# ADNS-9800_-_v2_1.net
KiCad netlist of a schematic drawn in EAGLE
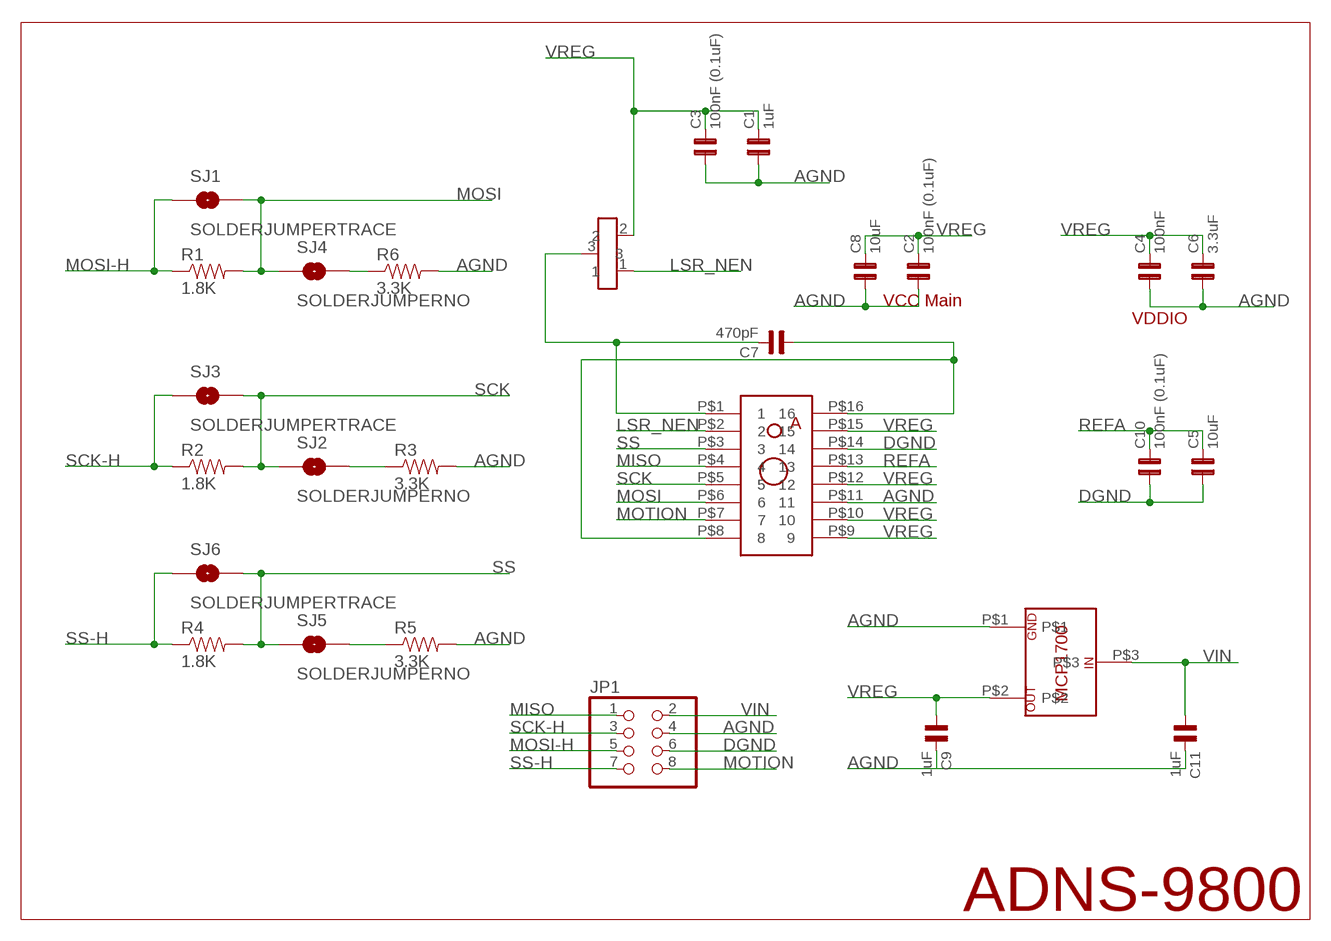
[diagram p0: schematic, sheet 1]

(export (version "E")
  (design (tool "Eeschema 10.0.6"))
  (components
    (comp (ref "C1")
      (value "1uF")
      (footprint "eagle-import:0603")
      (libsource (lib "eagle-import") (part "C0603"))
    )
    (comp (ref "C2")
      (value "100nF (0.1uF)")
      (footprint "eagle-import:0603")
      (libsource (lib "eagle-import") (part "C0603"))
    )
    (comp (ref "C3")
      (value "100nF (0.1uF)")
      (footprint "eagle-import:0603")
      (libsource (lib "eagle-import") (part "C0603"))
    )
    (comp (ref "C4")
      (value "100nF")
      (footprint "eagle-import:0603")
      (libsource (lib "eagle-import") (part "C0603"))
    )
    (comp (ref "C5")
      (value "10uF")
      (footprint "eagle-import:0603")
      (libsource (lib "eagle-import") (part "C0603"))
    )
    (comp (ref "C6")
      (value "3.3uF")
      (footprint "eagle-import:0603")
      (libsource (lib "eagle-import") (part "C0603"))
    )
    (comp (ref "C7")
      (value "470pF")
      (footprint "eagle-import:0603")
      (libsource (lib "eagle-import") (part "C0603"))
    )
    (comp (ref "C8")
      (value "10uF")
      (footprint "eagle-import:0603")
      (libsource (lib "eagle-import") (part "C0603"))
    )
    (comp (ref "C9")
      (value "1uF")
      (footprint "eagle-import:0603")
      (libsource (lib "eagle-import") (part "C0603"))
    )
    (comp (ref "C10")
      (value "100nF (0.1uF)")
      (footprint "eagle-import:0603")
      (libsource (lib "eagle-import") (part "C0603"))
    )
    (comp (ref "C11")
      (value "1uF")
      (footprint "eagle-import:0603")
      (libsource (lib "eagle-import") (part "C0603"))
    )
    (comp (ref "JP1")
      (value "PINHD-2X4")
      (footprint "eagle-import:2X04")
      (libsource (lib "eagle-import") (part "PINHD-2X4"))
    )
    (comp (ref "Q1")
      (value "TRANSISTOR_SC-75")
      (footprint "eagle-import:SC-75_TRANSISTOR")
      (libsource (lib "eagle-import") (part "TRANSISTOR_SC-75"))
    )
    (comp (ref "R1")
      (value "1.8K")
      (footprint "eagle-import:0603-RES")
      (libsource (lib "eagle-import") (part "RESISTOR0603-RES"))
    )
    (comp (ref "R2")
      (value "1.8K")
      (footprint "eagle-import:0603-RES")
      (libsource (lib "eagle-import") (part "RESISTOR0603-RES"))
    )
    (comp (ref "R3")
      (value "3.3K")
      (footprint "eagle-import:0603-RES")
      (libsource (lib "eagle-import") (part "RESISTOR0603-RES"))
    )
    (comp (ref "R4")
      (value "1.8K")
      (footprint "eagle-import:0603-RES")
      (libsource (lib "eagle-import") (part "RESISTOR0603-RES"))
    )
    (comp (ref "R5")
      (value "3.3K")
      (footprint "eagle-import:0603-RES")
      (libsource (lib "eagle-import") (part "RESISTOR0603-RES"))
    )
    (comp (ref "R6")
      (value "3.3K")
      (footprint "eagle-import:0603-RES")
      (libsource (lib "eagle-import") (part "RESISTOR0603-RES"))
    )
    (comp (ref "SJ1")
      (value "SOLDERJUMPERTRACE")
      (footprint "eagle-import:SJ_2S-TRACE")
      (libsource (lib "eagle-import") (part "SOLDERJUMPERTRACE"))
    )
    (comp (ref "SJ2")
      (value "SOLDERJUMPERNO")
      (footprint "eagle-import:SJ_2S-NO")
      (libsource (lib "eagle-import") (part "SOLDERJUMPERNO"))
    )
    (comp (ref "SJ3")
      (value "SOLDERJUMPERTRACE")
      (footprint "eagle-import:SJ_2S-TRACE")
      (libsource (lib "eagle-import") (part "SOLDERJUMPERTRACE"))
    )
    (comp (ref "SJ4")
      (value "SOLDERJUMPERNO")
      (footprint "eagle-import:SJ_2S-NO")
      (libsource (lib "eagle-import") (part "SOLDERJUMPERNO"))
    )
    (comp (ref "SJ5")
      (value "SOLDERJUMPERNO")
      (footprint "eagle-import:SJ_2S-NO")
      (libsource (lib "eagle-import") (part "SOLDERJUMPERNO"))
    )
    (comp (ref "SJ6")
      (value "SOLDERJUMPERTRACE")
      (footprint "eagle-import:SJ_2S-TRACE")
      (libsource (lib "eagle-import") (part "SOLDERJUMPERTRACE"))
    )
    (comp (ref "U$1")
      (value "AVAGO_ADNS-9500")
      (footprint "eagle-import:AVAGO_ADNS-9500")
      (libsource (lib "eagle-import") (part "AVAGO_ADNS-9500"))
    )
    (comp (ref "U$2")
      (value "MCP1700__LDO")
      (footprint "eagle-import:MCP1700__LDO")
      (libsource (lib "eagle-import") (part "MCP1700__LDO"))
    )
  )
  (nets
    (net (code "1") (name "/AGND") (class "Default")
      (node (ref "C1") (pin "1") (pinfunction "1_1") (pintype "passive"))
      (node (ref "C11") (pin "2") (pinfunction "2_2") (pintype "passive"))
      (node (ref "C2") (pin "1") (pinfunction "1_1") (pintype "passive"))
      (node (ref "C3") (pin "1") (pinfunction "1_1") (pintype "passive"))
      (node (ref "C4") (pin "1") (pinfunction "1_1") (pintype "passive"))
      (node (ref "C6") (pin "1") (pinfunction "1_1") (pintype "passive"))
      (node (ref "C8") (pin "1") (pinfunction "1_1") (pintype "passive"))
      (node (ref "C9") (pin "2") (pinfunction "2_2") (pintype "passive"))
      (node (ref "JP1") (pin "4") (pinfunction "4_4") (pintype "passive"))
      (node (ref "R3") (pin "2") (pinfunction "2_2") (pintype "passive"))
      (node (ref "R5") (pin "2") (pinfunction "2_2") (pintype "passive"))
      (node (ref "R6") (pin "2") (pinfunction "2_2") (pintype "passive"))
      (node (ref "U$1") (pin "P$11") (pinfunction "11_P$11") (pintype "bidirectional"))
      (node (ref "U$2") (pin "P$1") (pinfunction "P$1_P$1") (pintype "bidirectional"))
    )
    (net (code "2") (name "/DGND") (class "Default")
      (node (ref "C10") (pin "1") (pinfunction "1_1") (pintype "passive"))
      (node (ref "C5") (pin "1") (pinfunction "1_1") (pintype "passive"))
      (node (ref "JP1") (pin "6") (pinfunction "6_6") (pintype "passive"))
      (node (ref "U$1") (pin "P$14") (pinfunction "14_P$14") (pintype "bidirectional"))
    )
    (net (code "3") (name "/LSR_NEN") (class "Default")
      (node (ref "Q1") (pin "1") (pinfunction "1_1") (pintype "bidirectional"))
      (node (ref "U$1") (pin "P$2") (pinfunction "2_P$2") (pintype "bidirectional"))
    )
    (net (code "4") (name "/MISO") (class "Default")
      (node (ref "JP1") (pin "1") (pinfunction "1_1") (pintype "passive"))
      (node (ref "U$1") (pin "P$4") (pinfunction "4_P$4") (pintype "bidirectional"))
    )
    (net (code "5") (name "/MOSI") (class "Default")
      (node (ref "R1") (pin "2") (pinfunction "2_2") (pintype "passive"))
      (node (ref "SJ1") (pin "2") (pinfunction "2_2") (pintype "passive"))
      (node (ref "SJ4") (pin "1") (pinfunction "1_1") (pintype "passive"))
      (node (ref "U$1") (pin "P$6") (pinfunction "6_P$6") (pintype "bidirectional"))
    )
    (net (code "6") (name "/MOSI-H") (class "Default")
      (node (ref "JP1") (pin "5") (pinfunction "5_5") (pintype "passive"))
      (node (ref "R1") (pin "1") (pinfunction "1_1") (pintype "passive"))
      (node (ref "SJ1") (pin "1") (pinfunction "1_1") (pintype "passive"))
    )
    (net (code "7") (name "/MOTION") (class "Default")
      (node (ref "JP1") (pin "8") (pinfunction "8_8") (pintype "passive"))
      (node (ref "U$1") (pin "P$7") (pinfunction "7_P$7") (pintype "bidirectional"))
    )
    (net (code "8") (name "/REFA") (class "Default")
      (node (ref "C10") (pin "2") (pinfunction "2_2") (pintype "passive"))
      (node (ref "C5") (pin "2") (pinfunction "2_2") (pintype "passive"))
      (node (ref "U$1") (pin "P$13") (pinfunction "13_P$13") (pintype "bidirectional"))
    )
    (net (code "9") (name "/SCK") (class "Default")
      (node (ref "R2") (pin "2") (pinfunction "2_2") (pintype "passive"))
      (node (ref "SJ2") (pin "1") (pinfunction "1_1") (pintype "passive"))
      (node (ref "SJ3") (pin "2") (pinfunction "2_2") (pintype "passive"))
      (node (ref "U$1") (pin "P$5") (pinfunction "5_P$5") (pintype "bidirectional"))
    )
    (net (code "10") (name "/SCK-H") (class "Default")
      (node (ref "JP1") (pin "3") (pinfunction "3_3") (pintype "passive"))
      (node (ref "R2") (pin "1") (pinfunction "1_1") (pintype "passive"))
      (node (ref "SJ3") (pin "1") (pinfunction "1_1") (pintype "passive"))
    )
    (net (code "11") (name "/SS") (class "Default")
      (node (ref "R4") (pin "2") (pinfunction "2_2") (pintype "passive"))
      (node (ref "SJ5") (pin "1") (pinfunction "1_1") (pintype "passive"))
      (node (ref "SJ6") (pin "2") (pinfunction "2_2") (pintype "passive"))
      (node (ref "U$1") (pin "P$3") (pinfunction "3_P$3") (pintype "bidirectional"))
    )
    (net (code "12") (name "/SS-H") (class "Default")
      (node (ref "JP1") (pin "7") (pinfunction "7_7") (pintype "passive"))
      (node (ref "R4") (pin "1") (pinfunction "1_1") (pintype "passive"))
      (node (ref "SJ6") (pin "1") (pinfunction "1_1") (pintype "passive"))
    )
    (net (code "13") (name "/VIN") (class "Default")
      (node (ref "C11") (pin "1") (pinfunction "1_1") (pintype "passive"))
      (node (ref "JP1") (pin "2") (pinfunction "2_2") (pintype "passive"))
      (node (ref "U$2") (pin "P$3") (pinfunction "P$3_P$3") (pintype "bidirectional"))
    )
    (net (code "14") (name "/VREG") (class "Default")
      (node (ref "C1") (pin "2") (pinfunction "2_2") (pintype "passive"))
      (node (ref "C2") (pin "2") (pinfunction "2_2") (pintype "passive"))
      (node (ref "C3") (pin "2") (pinfunction "2_2") (pintype "passive"))
      (node (ref "C4") (pin "2") (pinfunction "2_2") (pintype "passive"))
      (node (ref "C6") (pin "2") (pinfunction "2_2") (pintype "passive"))
      (node (ref "C8") (pin "2") (pinfunction "2_2") (pintype "passive"))
      (node (ref "C9") (pin "1") (pinfunction "1_1") (pintype "passive"))
      (node (ref "Q1") (pin "2") (pinfunction "2_2") (pintype "bidirectional"))
      (node (ref "U$1") (pin "P$10") (pinfunction "10_P$10") (pintype "bidirectional"))
      (node (ref "U$1") (pin "P$12") (pinfunction "12_P$12") (pintype "bidirectional"))
      (node (ref "U$1") (pin "P$15") (pinfunction "15_P$15") (pintype "bidirectional"))
      (node (ref "U$1") (pin "P$9") (pinfunction "9_P$9") (pintype "bidirectional"))
      (node (ref "U$2") (pin "P$2") (pinfunction "P$2_P$2") (pintype "bidirectional"))
    )
    (net (code "15") (name "Net-(R3-Pad1)") (class "Default")
      (node (ref "R3") (pin "1") (pinfunction "1_1") (pintype "passive"))
      (node (ref "SJ2") (pin "2") (pinfunction "2_2") (pintype "passive"))
    )
    (net (code "16") (name "Net-(R5-Pad1)") (class "Default")
      (node (ref "R5") (pin "1") (pinfunction "1_1") (pintype "passive"))
      (node (ref "SJ5") (pin "2") (pinfunction "2_2") (pintype "passive"))
    )
    (net (code "17") (name "Net-(R6-Pad1)") (class "Default")
      (node (ref "R6") (pin "1") (pinfunction "1_1") (pintype "passive"))
      (node (ref "SJ4") (pin "2") (pinfunction "2_2") (pintype "passive"))
    )
    (net (code "18") (name "Net-(U$1-1)") (class "Default")
      (node (ref "C7") (pin "2") (pinfunction "2_2") (pintype "passive"))
      (node (ref "Q1") (pin "3") (pinfunction "3_3") (pintype "bidirectional"))
      (node (ref "U$1") (pin "P$1") (pinfunction "1_P$1") (pintype "bidirectional"))
    )
    (net (code "19") (name "Net-(U$1-16)") (class "Default")
      (node (ref "C7") (pin "1") (pinfunction "1_1") (pintype "passive"))
      (node (ref "U$1") (pin "P$16") (pinfunction "16_P$16") (pintype "bidirectional"))
      (node (ref "U$1") (pin "P$8") (pinfunction "8_P$8") (pintype "bidirectional"))
    )
  )
)
